# TFillChecker.net
KiCad netlist of a schematic drawn in Altium Designer
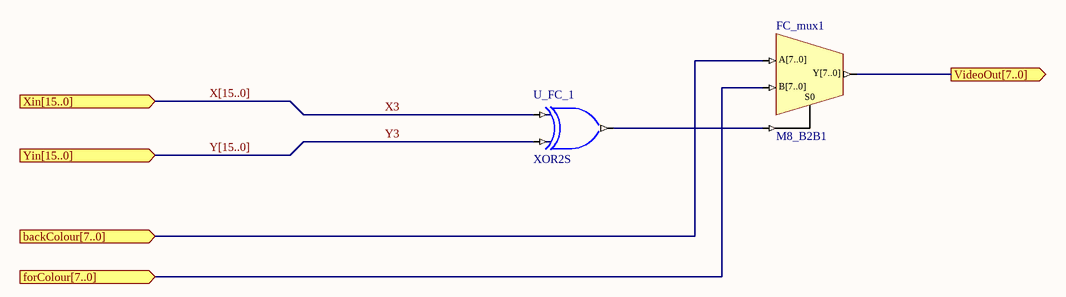
[diagram p0: TFillChecker.schDoc]

(export (version "E")
  (design (tool "Eeschema 10.0.6"))
  (components
    (comp (ref "FC_mux1")
      (value "M8_B2B1")
      (description "2x8-Bit Bus to 1x8-Bit Bus Multiplexer")
      (fields (field (name "PUBLISHER") "Altium Limited"))
      (libsource (lib "FPGA Generic") (part "M8_B2B1"))
    )
    (comp (ref "U_FC_1")
      (value "XOR2S")
      (description "2-Input Exclusive-OR Gate, Single Pin Version")
      (fields (field (name "PUBLISHER") "Altium Limited"))
      (libsource (lib "FPGA Generic") (part "XOR2S"))
    )
  )
  (nets
    (net (code "55") (name "/VideoOut[7..0]") (class "Default")
      (node (ref "FC_mux1") (pin "Y[7..0]") (pinfunction "Y[7..0]_Y[7..0]") (pintype "output"))
    )
    (net (code "56") (name "/X3") (class "Default")
      (node (ref "U_FC_1") (pin "I0") (pinfunction "I0_I0") (pintype "input"))
    )
    (net (code "58") (name "/Y3") (class "Default")
      (node (ref "U_FC_1") (pin "I1") (pinfunction "I1_I1") (pintype "input"))
    )
    (net (code "60") (name "/backColour[7..0]") (class "Default")
      (node (ref "FC_mux1") (pin "A[7..0]") (pinfunction "A[7..0]_A[7..0]") (pintype "input"))
    )
    (net (code "61") (name "/forColour[7..0]") (class "Default")
      (node (ref "FC_mux1") (pin "B[7..0]") (pinfunction "B[7..0]_B[7..0]") (pintype "input"))
    )
    (net (code "62") (name "Net-(FC_mux1-PadS0)") (class "Default")
      (node (ref "FC_mux1") (pin "S0") (pinfunction "S0_S0") (pintype "input"))
      (node (ref "U_FC_1") (pin "O") (pinfunction "O_O") (pintype "output"))
    )
  )
)
